# RM04-KITV.net
KiCad netlist of a schematic drawn in Altium Designer
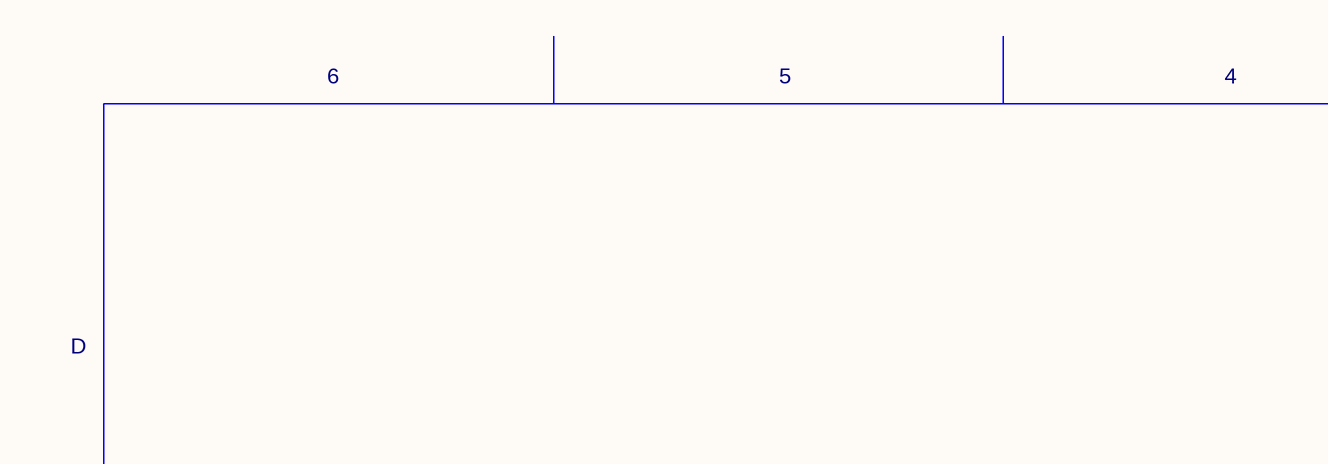
[diagram p0: RM04-KITV.SchDoc, top left]
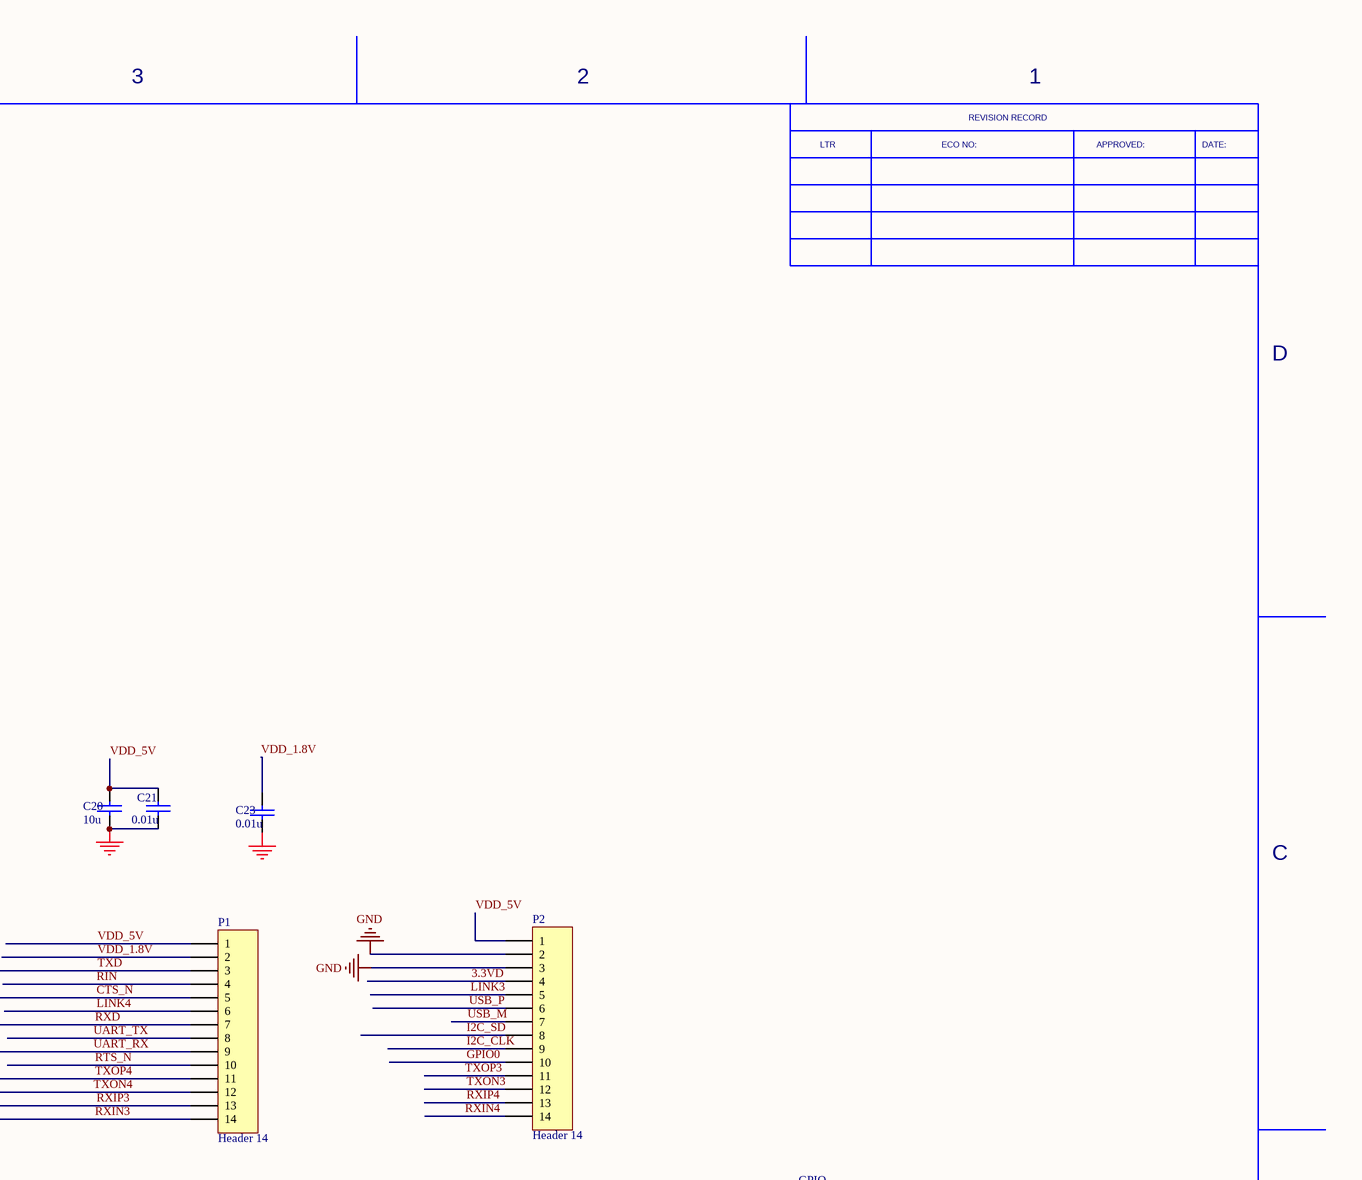
[diagram p1: RM04-KITV.SchDoc, top right]
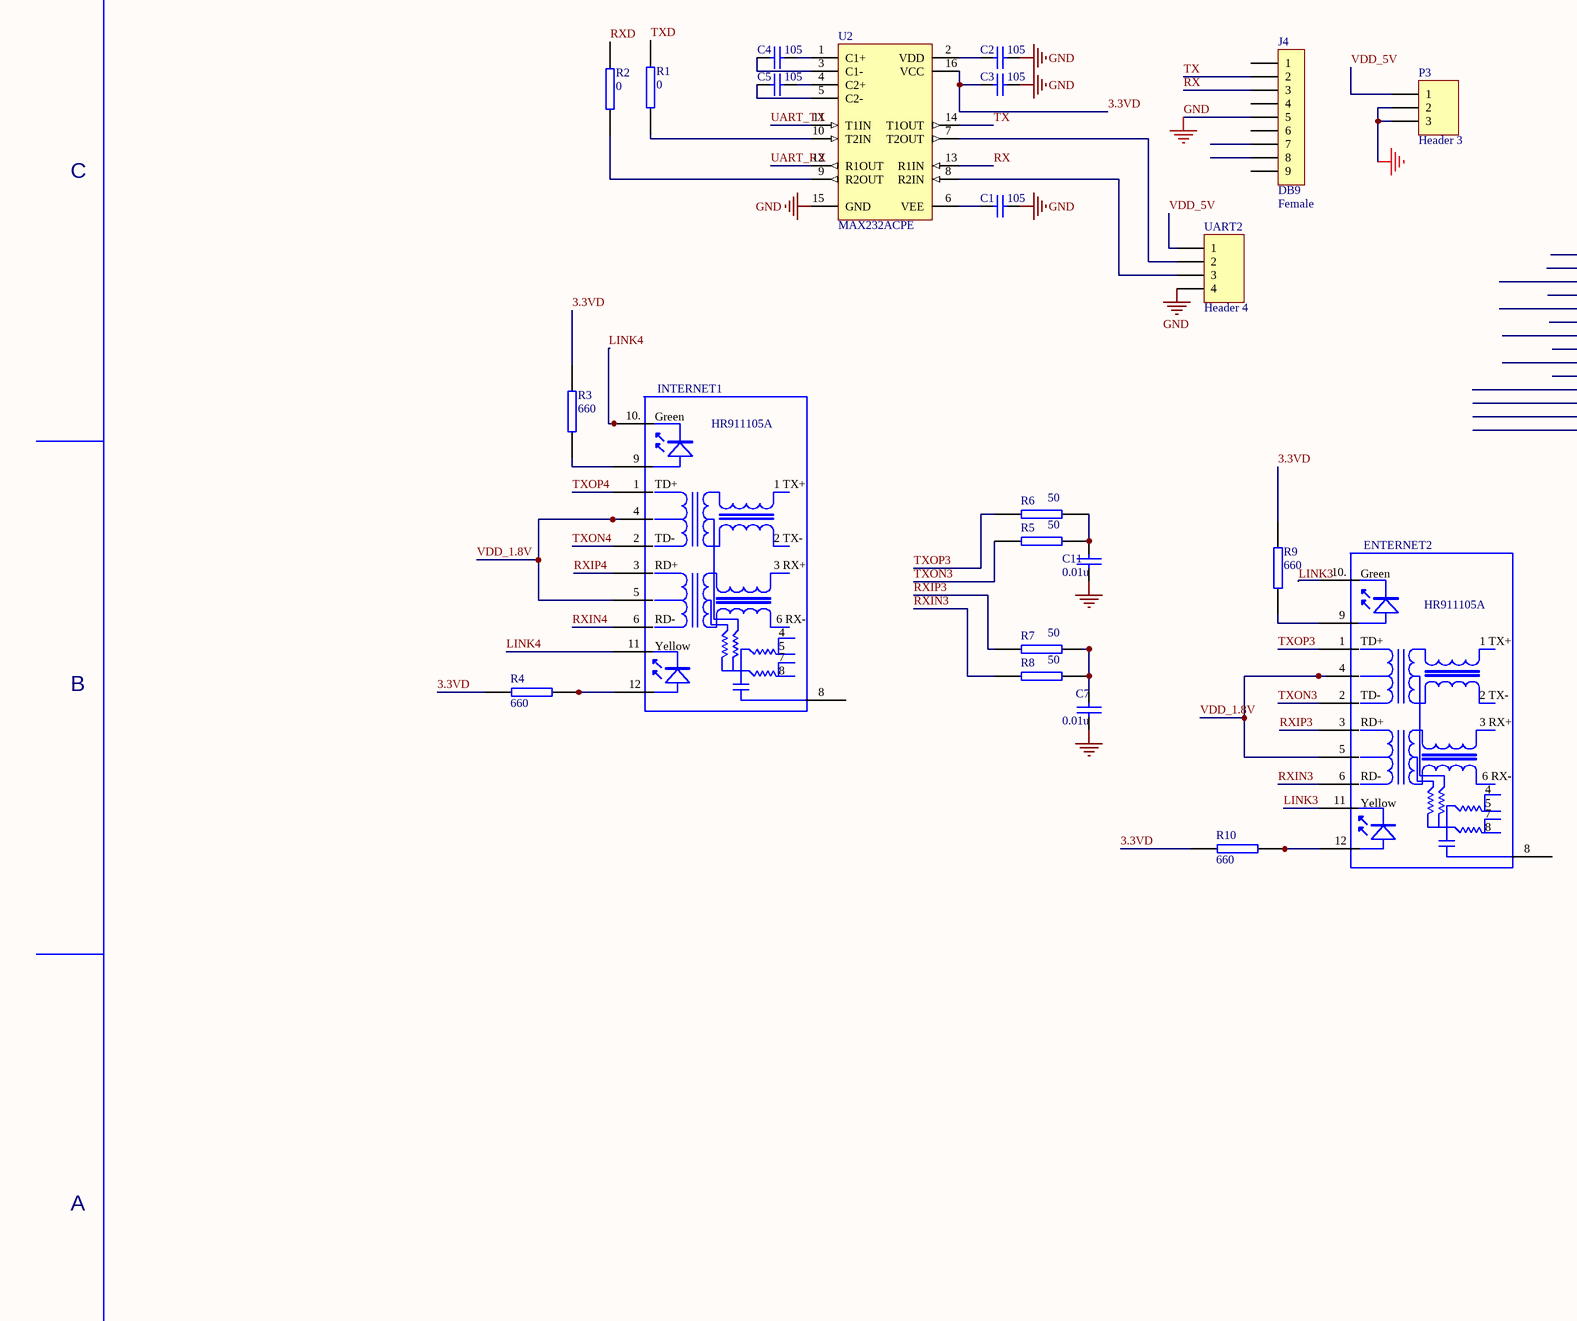
[diagram p2: RM04-KITV.SchDoc, bottom left]
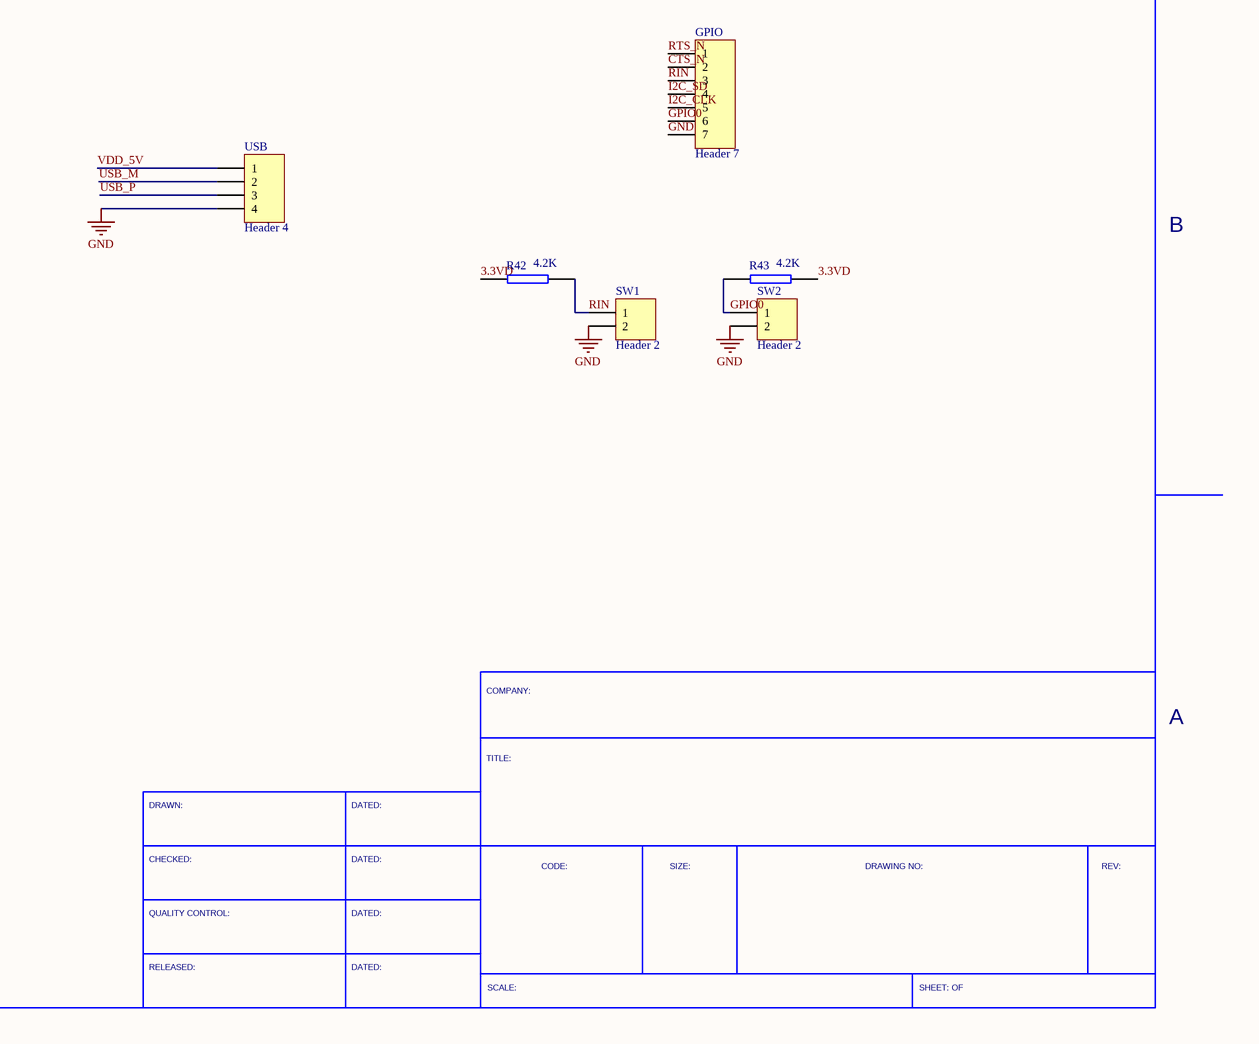
[diagram p3: RM04-KITV.SchDoc, bottom right]

(export (version "E")
  (design (tool "Eeschema 10.0.6"))
  (components
    (comp (ref "C1")
      (value "105")
      (footprint "0603")
      (description "Capacitor")
      (fields (field (name "PUBLISHER") "Altium Limited"))
      (libsource (lib "Miscellaneous Devices") (part "Cap"))
    )
    (comp (ref "C2")
      (value "105")
      (footprint "0603")
      (description "Capacitor")
      (fields (field (name "PUBLISHER") "Altium Limited"))
      (libsource (lib "Miscellaneous Devices") (part "Cap"))
    )
    (comp (ref "C3")
      (value "105")
      (footprint "0603")
      (description "Capacitor")
      (fields (field (name "PUBLISHER") "Altium Limited"))
      (libsource (lib "Miscellaneous Devices") (part "Cap"))
    )
    (comp (ref "C4")
      (value "105")
      (footprint "0603")
      (description "Capacitor")
      (fields (field (name "PUBLISHER") "Altium Limited"))
      (libsource (lib "Miscellaneous Devices") (part "Cap"))
    )
    (comp (ref "C5")
      (value "105")
      (footprint "0603")
      (description "Capacitor")
      (fields (field (name "PUBLISHER") "Altium Limited"))
      (libsource (lib "Miscellaneous Devices") (part "Cap"))
    )
    (comp (ref "C7")
      (value "0.01u")
      (footprint "0603")
      (description "Capacitor")
      (libsource (lib "*") (part "CAP"))
    )
    (comp (ref "C11")
      (value "0.01u")
      (footprint "0603")
      (description "Capacitor")
      (libsource (lib "*") (part "CAP"))
    )
    (comp (ref "C20")
      (value "10u")
      (footprint "0805")
      (description "Capacitor")
      (libsource (lib "*") (part "CAP"))
    )
    (comp (ref "C21")
      (value "0.01u")
      (footprint "0603")
      (description "Capacitor")
      (libsource (lib "*") (part "CAP"))
    )
    (comp (ref "C23")
      (value "0.01u")
      (footprint "0603")
      (description "Capacitor")
      (libsource (lib "*") (part "CAP"))
    )
    (comp (ref "ENTERNET2")
      (value "HR911105A")
      (footprint "HR911105A")
      (libsource (lib "*") (part "HR911105A"))
    )
    (comp (ref "GPIO")
      (value "Header 7")
      (footprint "HDR1X7")
      (description "Header, 7-Pin")
      (fields (field (name "PUBLISHER") "Altium Limited"))
      (libsource (lib "Miscellaneous Connectors") (part "Header 7"))
    )
    (comp (ref "INTERNET1")
      (value "HR911105A")
      (footprint "HR911105A")
      (libsource (lib "*") (part "HR911105A"))
    )
    (comp (ref "J4")
      (value "DB9")
      (footprint "DB9S")
      (description "Connector")
      (libsource (lib "*") (part "CON9"))
    )
    (comp (ref "P1")
      (value "Header 14")
      (footprint "H1*14-2.0")
      (description "Header, 14-Pin")
      (fields (field (name "PUBLISHER") "Altium Limited"))
      (libsource (lib "Miscellaneous Connectors") (part "Header 14"))
    )
    (comp (ref "P2")
      (value "Header 14")
      (footprint "H1*14-2.0")
      (description "Header, 14-Pin")
      (fields (field (name "PUBLISHER") "Altium Limited"))
      (libsource (lib "Miscellaneous Connectors") (part "Header 14"))
    )
    (comp (ref "P3")
      (value "Header 3")
      (footprint "POWER_STK1")
      (description "Header, 3-Pin")
      (fields (field (name "PUBLISHER") "Altium Limited"))
      (libsource (lib "Miscellaneous Connectors") (part "Header 3"))
    )
    (comp (ref "R1") (value "0") (footprint "0603") (libsource (lib "*") (part "RES2")))
    (comp (ref "R2") (value "0") (footprint "0603") (libsource (lib "*") (part "RES2")))
    (comp (ref "R3") (value "660") (footprint "0603") (libsource (lib "*") (part "RES2")))
    (comp (ref "R4") (value "660") (footprint "0603") (libsource (lib "*") (part "RES2")))
    (comp (ref "R5") (value "50") (footprint "0603") (libsource (lib "*") (part "RES2")))
    (comp (ref "R6") (value "50") (footprint "0603") (libsource (lib "*") (part "RES2")))
    (comp (ref "R7") (value "50") (footprint "0603") (libsource (lib "*") (part "RES2")))
    (comp (ref "R8") (value "50") (footprint "0603") (libsource (lib "*") (part "RES2")))
    (comp (ref "R9") (value "660") (footprint "0603") (libsource (lib "*") (part "RES2")))
    (comp (ref "R10") (value "660") (footprint "0603") (libsource (lib "*") (part "RES2")))
    (comp (ref "R42") (value "4.2K") (footprint "0603") (libsource (lib "*") (part "RES2")))
    (comp (ref "R43") (value "4.2K") (footprint "0603") (libsource (lib "*") (part "RES2")))
    (comp (ref "SW1")
      (value "Header 2")
      (footprint "HDR1X2")
      (description "Header, 2-Pin")
      (fields (field (name "PUBLISHER") "Altium Limited"))
      (libsource (lib "Miscellaneous Connectors") (part "Header 2"))
    )
    (comp (ref "SW2")
      (value "Header 2")
      (footprint "HDR1X2")
      (description "Header, 2-Pin")
      (fields (field (name "PUBLISHER") "Altium Limited"))
      (libsource (lib "Miscellaneous Connectors") (part "Header 2"))
    )
    (comp (ref "U2")
      (value "MAX232ACPE")
      (footprint "SOP-16")
      (description "+5V Powered, Multi-Channel RS-232 Driver/Receiver")
      (fields (field (name "PUBLISHER") "Altium Limited"))
      (libsource (lib "Maxim Communication Transceiver") (part "MAX232ACPE"))
    )
    (comp (ref "UART2")
      (value "Header 4")
      (footprint "HDR1X4")
      (description "Header, 4-Pin")
      (fields (field (name "PUBLISHER") "Altium Limited"))
      (libsource (lib "Miscellaneous Connectors") (part "Header 4"))
    )
    (comp (ref "USB")
      (value "Header 4")
      (footprint "USB_A")
      (description "Header, 4-Pin")
      (fields (field (name "PUBLISHER") "Altium Limited"))
      (libsource (lib "Miscellaneous Connectors") (part "Header 4"))
    )
  )
  (nets
    (net (code "1") (name "/3.3VD") (class "Default")
      (node (ref "C3") (pin "2") (pinfunction "2_2") (pintype "passive"))
      (node (ref "P2") (pin "4") (pinfunction "4_4") (pintype "passive"))
      (node (ref "R10") (pin "2") (pinfunction "2_2") (pintype "passive"))
      (node (ref "R3") (pin "1") (pinfunction "1_1") (pintype "passive"))
      (node (ref "R4") (pin "2") (pinfunction "2_2") (pintype "passive"))
      (node (ref "R42") (pin "2") (pinfunction "2_2") (pintype "passive"))
      (node (ref "R43") (pin "1") (pinfunction "1_1") (pintype "passive"))
      (node (ref "R9") (pin "1") (pinfunction "1_1") (pintype "passive"))
      (node (ref "U2") (pin "16") (pinfunction "VCC_16") (pintype "power_in"))
    )
    (net (code "2") (name "/CTS_N") (class "Default")
      (node (ref "GPIO") (pin "2") (pinfunction "2_2") (pintype "passive"))
      (node (ref "P1") (pin "5") (pinfunction "5_5") (pintype "passive"))
    )
    (net (code "3") (name "/GPIO0") (class "Default")
      (node (ref "GPIO") (pin "6") (pinfunction "6_6") (pintype "passive"))
      (node (ref "P2") (pin "10") (pinfunction "10_10") (pintype "passive"))
      (node (ref "R43") (pin "2") (pinfunction "2_2") (pintype "passive"))
      (node (ref "SW2") (pin "1") (pinfunction "1_1") (pintype "passive"))
    )
    (net (code "4") (name "/I2C_CLK") (class "Default")
      (node (ref "GPIO") (pin "5") (pinfunction "5_5") (pintype "passive"))
      (node (ref "P2") (pin "9") (pinfunction "9_9") (pintype "passive"))
    )
    (net (code "5") (name "/I2C_SD") (class "Default")
      (node (ref "GPIO") (pin "4") (pinfunction "4_4") (pintype "passive"))
      (node (ref "P2") (pin "8") (pinfunction "8_8") (pintype "passive"))
    )
    (net (code "6") (name "/LINK3") (class "Default")
      (node (ref "ENTERNET2") (pin "10.") (pintype "passive"))
      (node (ref "ENTERNET2") (pin "11") (pintype "passive"))
      (node (ref "P2") (pin "5") (pinfunction "5_5") (pintype "passive"))
    )
    (net (code "7") (name "/LINK4") (class "Default")
      (node (ref "INTERNET1") (pin "10.") (pintype "passive"))
      (node (ref "INTERNET1") (pin "11") (pintype "passive"))
      (node (ref "P1") (pin "6") (pinfunction "6_6") (pintype "passive"))
    )
    (net (code "8") (name "/RIN") (class "Default")
      (node (ref "GPIO") (pin "3") (pinfunction "3_3") (pintype "passive"))
      (node (ref "P1") (pin "4") (pinfunction "4_4") (pintype "passive"))
      (node (ref "R42") (pin "1") (pinfunction "1_1") (pintype "passive"))
      (node (ref "SW1") (pin "1") (pinfunction "1_1") (pintype "passive"))
    )
    (net (code "9") (name "/RTS_N") (class "Default")
      (node (ref "GPIO") (pin "1") (pinfunction "1_1") (pintype "passive"))
      (node (ref "P1") (pin "10") (pinfunction "10_10") (pintype "passive"))
    )
    (net (code "10") (name "/RX") (class "Default")
      (node (ref "J4") (pin "3") (pinfunction "3_3") (pintype "passive"))
      (node (ref "U2") (pin "13") (pinfunction "R1IN_13") (pintype "input"))
    )
    (net (code "11") (name "/RXD") (class "Default")
      (node (ref "P1") (pin "7") (pinfunction "7_7") (pintype "passive"))
      (node (ref "R2") (pin "2") (pinfunction "2_2") (pintype "passive"))
    )
    (net (code "12") (name "/RXIN3") (class "Default")
      (node (ref "ENTERNET2") (pin "6") (pintype "passive"))
      (node (ref "P1") (pin "14") (pinfunction "14_14") (pintype "passive"))
      (node (ref "R8") (pin "1") (pinfunction "1_1") (pintype "passive"))
    )
    (net (code "13") (name "/RXIN4") (class "Default")
      (node (ref "INTERNET1") (pin "6") (pintype "passive"))
      (node (ref "P2") (pin "14") (pinfunction "14_14") (pintype "passive"))
    )
    (net (code "14") (name "/RXIP3") (class "Default")
      (node (ref "ENTERNET2") (pin "3") (pintype "passive"))
      (node (ref "P1") (pin "13") (pinfunction "13_13") (pintype "passive"))
      (node (ref "R7") (pin "1") (pinfunction "1_1") (pintype "passive"))
    )
    (net (code "15") (name "/RXIP4") (class "Default")
      (node (ref "INTERNET1") (pin "3") (pintype "passive"))
      (node (ref "P2") (pin "13") (pinfunction "13_13") (pintype "passive"))
    )
    (net (code "16") (name "/TX") (class "Default")
      (node (ref "J4") (pin "2") (pinfunction "2_2") (pintype "passive"))
      (node (ref "U2") (pin "14") (pinfunction "T1OUT_14") (pintype "output"))
    )
    (net (code "17") (name "/TXD") (class "Default")
      (node (ref "P1") (pin "3") (pinfunction "3_3") (pintype "passive"))
      (node (ref "R1") (pin "2") (pinfunction "2_2") (pintype "passive"))
    )
    (net (code "18") (name "/TXON3") (class "Default")
      (node (ref "ENTERNET2") (pin "2") (pintype "passive"))
      (node (ref "P2") (pin "12") (pinfunction "12_12") (pintype "passive"))
      (node (ref "R5") (pin "1") (pinfunction "1_1") (pintype "passive"))
    )
    (net (code "19") (name "/TXON4") (class "Default")
      (node (ref "INTERNET1") (pin "2") (pintype "passive"))
      (node (ref "P1") (pin "12") (pinfunction "12_12") (pintype "passive"))
    )
    (net (code "20") (name "/TXOP3") (class "Default")
      (node (ref "ENTERNET2") (pin "1") (pintype "passive"))
      (node (ref "P2") (pin "11") (pinfunction "11_11") (pintype "passive"))
      (node (ref "R6") (pin "2") (pinfunction "2_2") (pintype "passive"))
    )
    (net (code "21") (name "/TXOP4") (class "Default")
      (node (ref "INTERNET1") (pin "1") (pintype "passive"))
      (node (ref "P1") (pin "11") (pinfunction "11_11") (pintype "passive"))
    )
    (net (code "22") (name "/UART_RX") (class "Default")
      (node (ref "P1") (pin "9") (pinfunction "9_9") (pintype "passive"))
      (node (ref "U2") (pin "12") (pinfunction "R1OUT_12") (pintype "output"))
    )
    (net (code "23") (name "/UART_TX") (class "Default")
      (node (ref "P1") (pin "8") (pinfunction "8_8") (pintype "passive"))
      (node (ref "U2") (pin "11") (pinfunction "T1IN_11") (pintype "input"))
    )
    (net (code "24") (name "/USB_M") (class "Default")
      (node (ref "P2") (pin "7") (pinfunction "7_7") (pintype "passive"))
      (node (ref "USB") (pin "2") (pinfunction "2_2") (pintype "passive"))
    )
    (net (code "25") (name "/USB_P") (class "Default")
      (node (ref "P2") (pin "6") (pinfunction "6_6") (pintype "passive"))
      (node (ref "USB") (pin "3") (pinfunction "3_3") (pintype "passive"))
    )
    (net (code "26") (name "/VDD_1.8V") (class "Default")
      (node (ref "C23") (pin "2") (pinfunction "2_2") (pintype "passive"))
      (node (ref "ENTERNET2") (pin "4") (pintype "passive"))
      (node (ref "ENTERNET2") (pin "5") (pintype "passive"))
      (node (ref "INTERNET1") (pin "4") (pintype "passive"))
      (node (ref "INTERNET1") (pin "5") (pintype "passive"))
      (node (ref "P1") (pin "2") (pinfunction "2_2") (pintype "passive"))
    )
    (net (code "27") (name "/VDD_5V") (class "Default")
      (node (ref "C20") (pin "2") (pinfunction "2_2") (pintype "passive"))
      (node (ref "C21") (pin "2") (pinfunction "2_2") (pintype "passive"))
      (node (ref "P1") (pin "1") (pinfunction "1_1") (pintype "passive"))
      (node (ref "P2") (pin "1") (pinfunction "1_1") (pintype "passive"))
      (node (ref "P3") (pin "1") (pinfunction "1_1") (pintype "passive"))
      (node (ref "UART2") (pin "1") (pinfunction "1_1") (pintype "passive"))
      (node (ref "USB") (pin "1") (pinfunction "1_1") (pintype "passive"))
    )
    (net (code "28") (name "GND") (class "Default")
      (node (ref "C1") (pin "1") (pinfunction "1_1") (pintype "passive"))
      (node (ref "C11") (pin "1") (pinfunction "1_1") (pintype "passive"))
      (node (ref "C2") (pin "1") (pinfunction "1_1") (pintype "passive"))
      (node (ref "C20") (pin "1") (pinfunction "1_1") (pintype "passive"))
      (node (ref "C21") (pin "1") (pinfunction "1_1") (pintype "passive"))
      (node (ref "C23") (pin "1") (pinfunction "1_1") (pintype "passive"))
      (node (ref "C3") (pin "1") (pinfunction "1_1") (pintype "passive"))
      (node (ref "C7") (pin "1") (pinfunction "1_1") (pintype "passive"))
      (node (ref "GPIO") (pin "7") (pinfunction "7_7") (pintype "passive"))
      (node (ref "J4") (pin "5") (pinfunction "5_5") (pintype "passive"))
      (node (ref "P2") (pin "2") (pinfunction "2_2") (pintype "passive"))
      (node (ref "P2") (pin "3") (pinfunction "3_3") (pintype "passive"))
      (node (ref "P3") (pin "2") (pinfunction "2_2") (pintype "passive"))
      (node (ref "P3") (pin "3") (pinfunction "3_3") (pintype "passive"))
      (node (ref "SW1") (pin "2") (pinfunction "2_2") (pintype "passive"))
      (node (ref "SW2") (pin "2") (pinfunction "2_2") (pintype "passive"))
      (node (ref "U2") (pin "15") (pinfunction "GND_15") (pintype "power_in"))
      (node (ref "UART2") (pin "4") (pinfunction "4_4") (pintype "passive"))
      (node (ref "USB") (pin "4") (pinfunction "4_4") (pintype "passive"))
    )
    (net (code "29") (name "Net-(C7-Pad2)") (class "Default")
      (node (ref "C7") (pin "2") (pinfunction "2_2") (pintype "passive"))
      (node (ref "R7") (pin "2") (pinfunction "2_2") (pintype "passive"))
      (node (ref "R8") (pin "2") (pinfunction "2_2") (pintype "passive"))
    )
    (net (code "30") (name "Net-(C11-Pad2)") (class "Default")
      (node (ref "C11") (pin "2") (pinfunction "2_2") (pintype "passive"))
      (node (ref "R5") (pin "2") (pinfunction "2_2") (pintype "passive"))
      (node (ref "R6") (pin "1") (pinfunction "1_1") (pintype "passive"))
    )
    (net (code "31") (name "Net-(ENTERNET2-Pad9)") (class "Default")
      (node (ref "ENTERNET2") (pin "9") (pintype "passive"))
      (node (ref "R9") (pin "2") (pinfunction "2_2") (pintype "passive"))
    )
    (net (code "32") (name "Net-(ENTERNET2-Pad12)") (class "Default")
      (node (ref "ENTERNET2") (pin "12") (pintype "passive"))
      (node (ref "R10") (pin "1") (pinfunction "1_1") (pintype "passive"))
    )
    (net (code "33") (name "Net-(INTERNET1-Pad9)") (class "Default")
      (node (ref "INTERNET1") (pin "9") (pintype "passive"))
      (node (ref "R3") (pin "2") (pinfunction "2_2") (pintype "passive"))
    )
    (net (code "34") (name "Net-(INTERNET1-Pad12)") (class "Default")
      (node (ref "INTERNET1") (pin "12") (pintype "passive"))
      (node (ref "R4") (pin "1") (pinfunction "1_1") (pintype "passive"))
    )
    (net (code "35") (name "Net-(U2-C1+)") (class "Default")
      (node (ref "C4") (pin "1") (pinfunction "1_1") (pintype "passive"))
      (node (ref "U2") (pin "1") (pinfunction "C1+_1") (pintype "passive"))
    )
    (net (code "36") (name "Net-(U2-C1-)") (class "Default")
      (node (ref "C4") (pin "2") (pinfunction "2_2") (pintype "passive"))
      (node (ref "U2") (pin "3") (pinfunction "C1-_3") (pintype "passive"))
    )
    (net (code "37") (name "Net-(U2-C2+)") (class "Default")
      (node (ref "C5") (pin "1") (pinfunction "1_1") (pintype "passive"))
      (node (ref "U2") (pin "4") (pinfunction "C2+_4") (pintype "passive"))
    )
    (net (code "38") (name "Net-(U2-C2-)") (class "Default")
      (node (ref "C5") (pin "2") (pinfunction "2_2") (pintype "passive"))
      (node (ref "U2") (pin "5") (pinfunction "C2-_5") (pintype "passive"))
    )
    (net (code "39") (name "Net-(U2-R2IN)") (class "Default")
      (node (ref "U2") (pin "8") (pinfunction "R2IN_8") (pintype "input"))
      (node (ref "UART2") (pin "3") (pinfunction "3_3") (pintype "passive"))
    )
    (net (code "40") (name "Net-(U2-R2OUT)") (class "Default")
      (node (ref "R2") (pin "1") (pinfunction "1_1") (pintype "passive"))
      (node (ref "U2") (pin "9") (pinfunction "R2OUT_9") (pintype "output"))
    )
    (net (code "41") (name "Net-(U2-T2IN)") (class "Default")
      (node (ref "R1") (pin "1") (pinfunction "1_1") (pintype "passive"))
      (node (ref "U2") (pin "10") (pinfunction "T2IN_10") (pintype "input"))
    )
    (net (code "42") (name "Net-(U2-T2OUT)") (class "Default")
      (node (ref "U2") (pin "7") (pinfunction "T2OUT_7") (pintype "output"))
      (node (ref "UART2") (pin "2") (pinfunction "2_2") (pintype "passive"))
    )
    (net (code "43") (name "Net-(U2-VDD)") (class "Default")
      (node (ref "C2") (pin "2") (pinfunction "2_2") (pintype "passive"))
      (node (ref "U2") (pin "2") (pinfunction "VDD_2") (pintype "power_in"))
    )
    (net (code "44") (name "Net-(U2-VEE)") (class "Default")
      (node (ref "C1") (pin "2") (pinfunction "2_2") (pintype "passive"))
      (node (ref "U2") (pin "6") (pinfunction "VEE_6") (pintype "power_in"))
    )
    (net (code "45") (name "unconnected-(ENTERNET2-Pad8)") (class "Default")
      (node (ref "ENTERNET2") (pin "8") (pintype "passive"))
    )
    (net (code "46") (name "unconnected-(INTERNET1-Pad8)") (class "Default")
      (node (ref "INTERNET1") (pin "8") (pintype "passive"))
    )
    (net (code "47") (name "unconnected-(J4-Pad1)") (class "Default")
      (node (ref "J4") (pin "1") (pinfunction "1_1") (pintype "passive"))
    )
    (net (code "48") (name "unconnected-(J4-Pad4)") (class "Default")
      (node (ref "J4") (pin "4") (pinfunction "4_4") (pintype "passive"))
    )
    (net (code "49") (name "unconnected-(J4-Pad6)") (class "Default")
      (node (ref "J4") (pin "6") (pinfunction "6_6") (pintype "passive"))
    )
    (net (code "50") (name "unconnected-(J4-Pad7)") (class "Default")
      (node (ref "J4") (pin "7") (pinfunction "7_7") (pintype "passive"))
    )
    (net (code "51") (name "unconnected-(J4-Pad8)") (class "Default")
      (node (ref "J4") (pin "8") (pinfunction "8_8") (pintype "passive"))
    )
    (net (code "52") (name "unconnected-(J4-Pad9)") (class "Default")
      (node (ref "J4") (pin "9") (pinfunction "9_9") (pintype "passive"))
    )
  )
)
